# Box-3_Electronics_v5.net
KiCad netlist of a schematic drawn in EAGLE
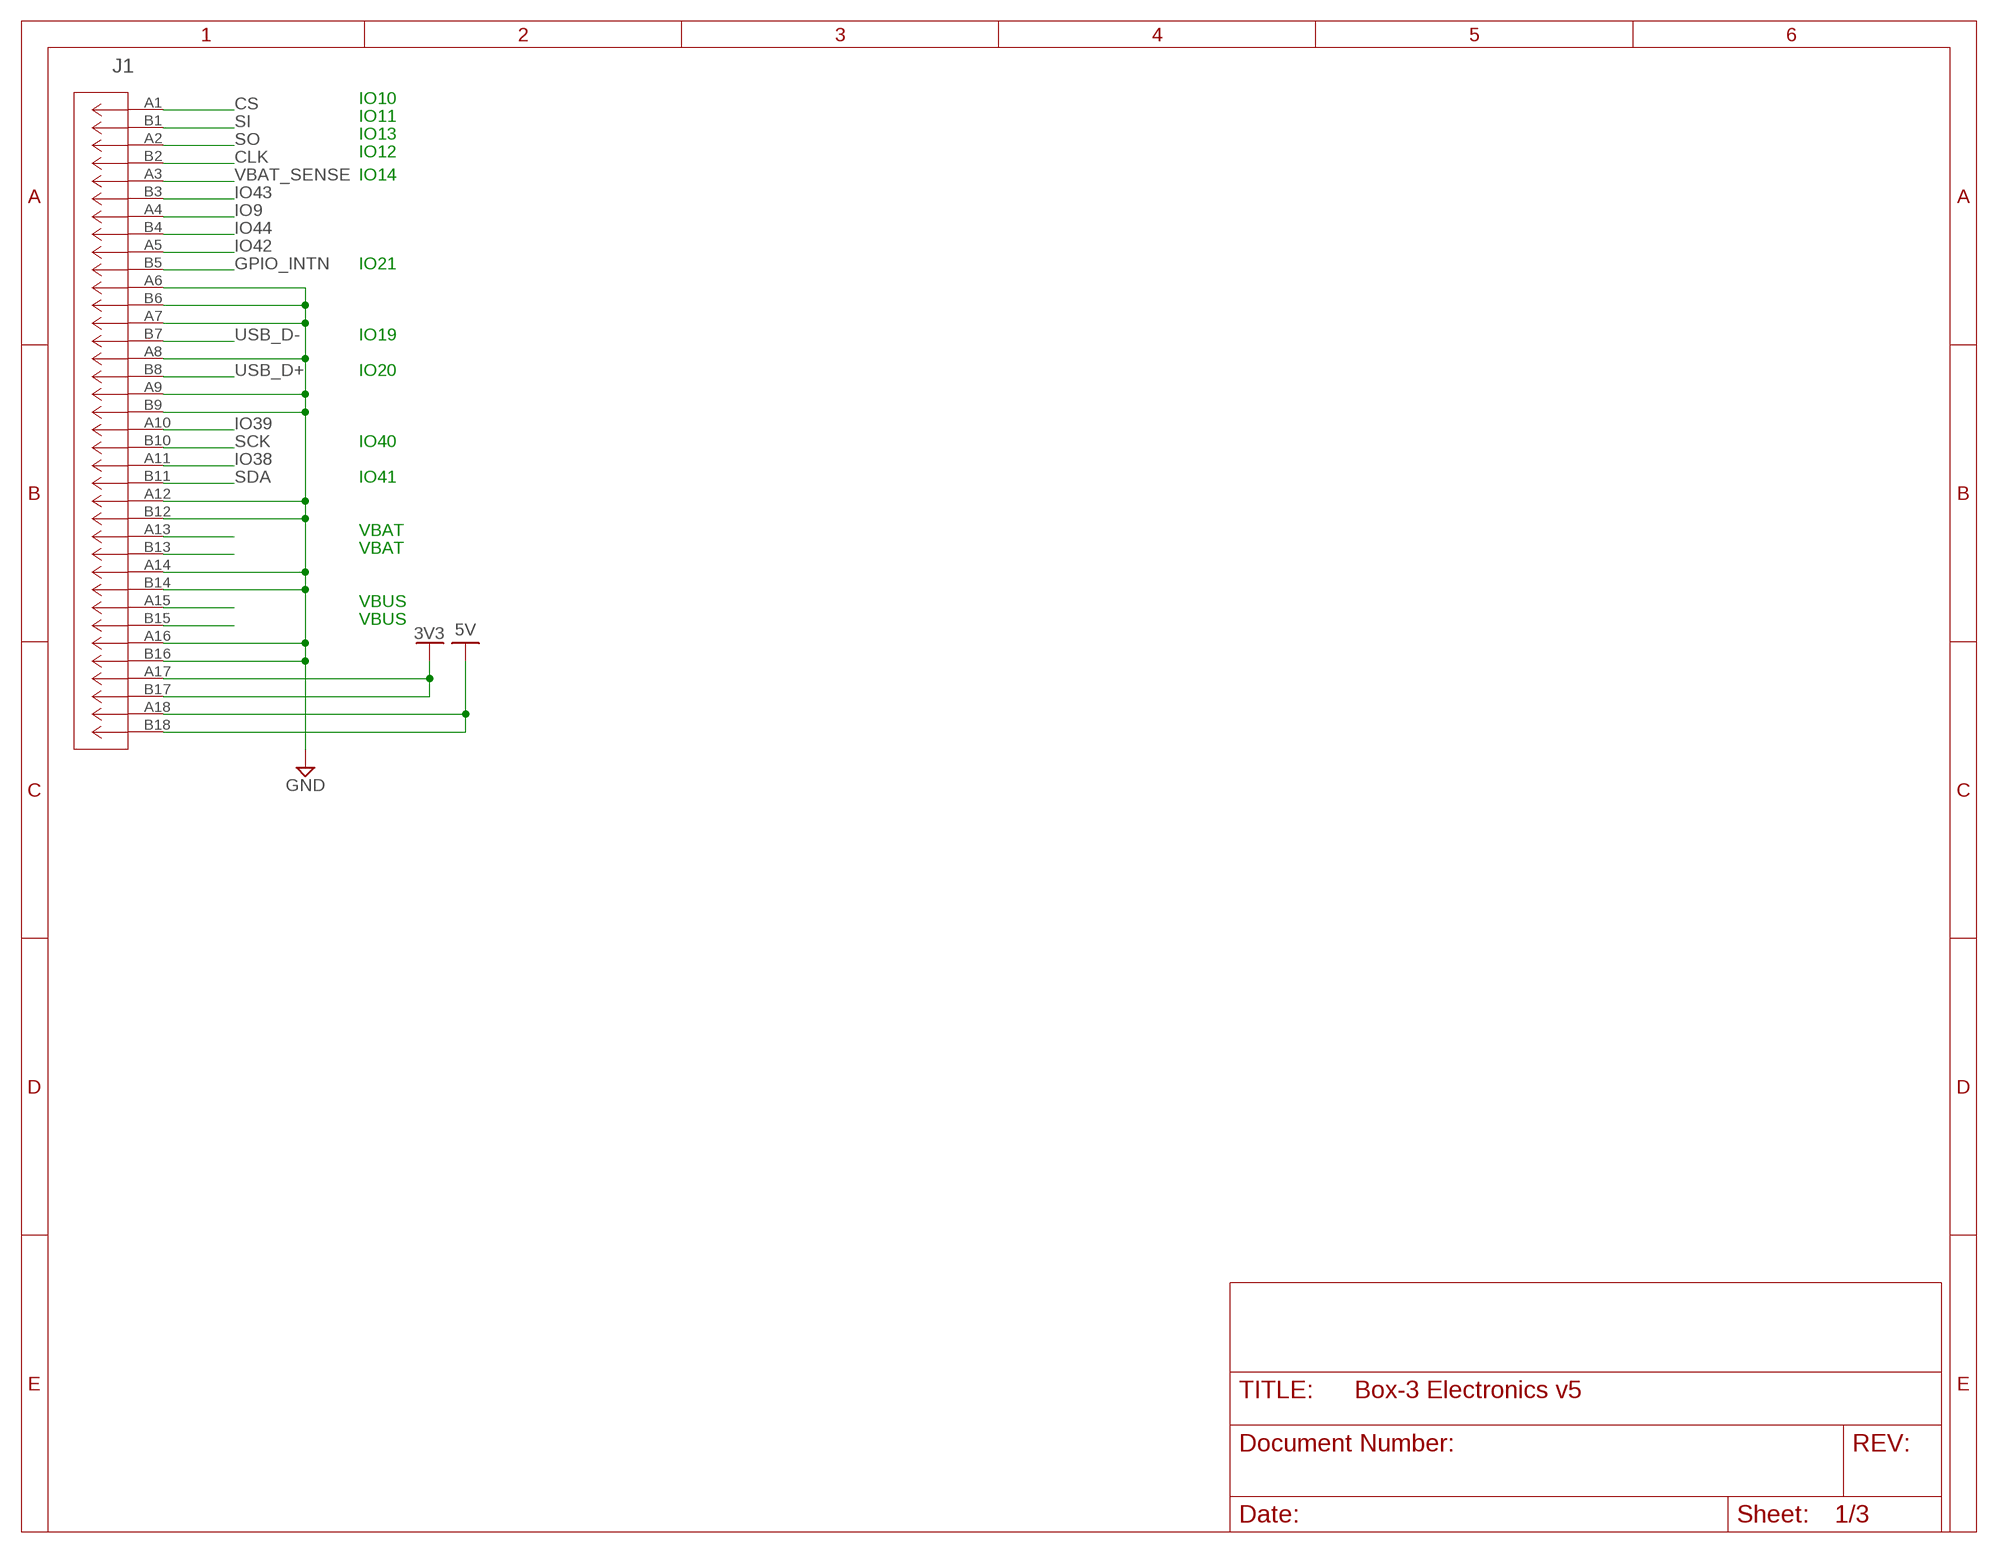
[diagram p0: schematic, sheet 1]
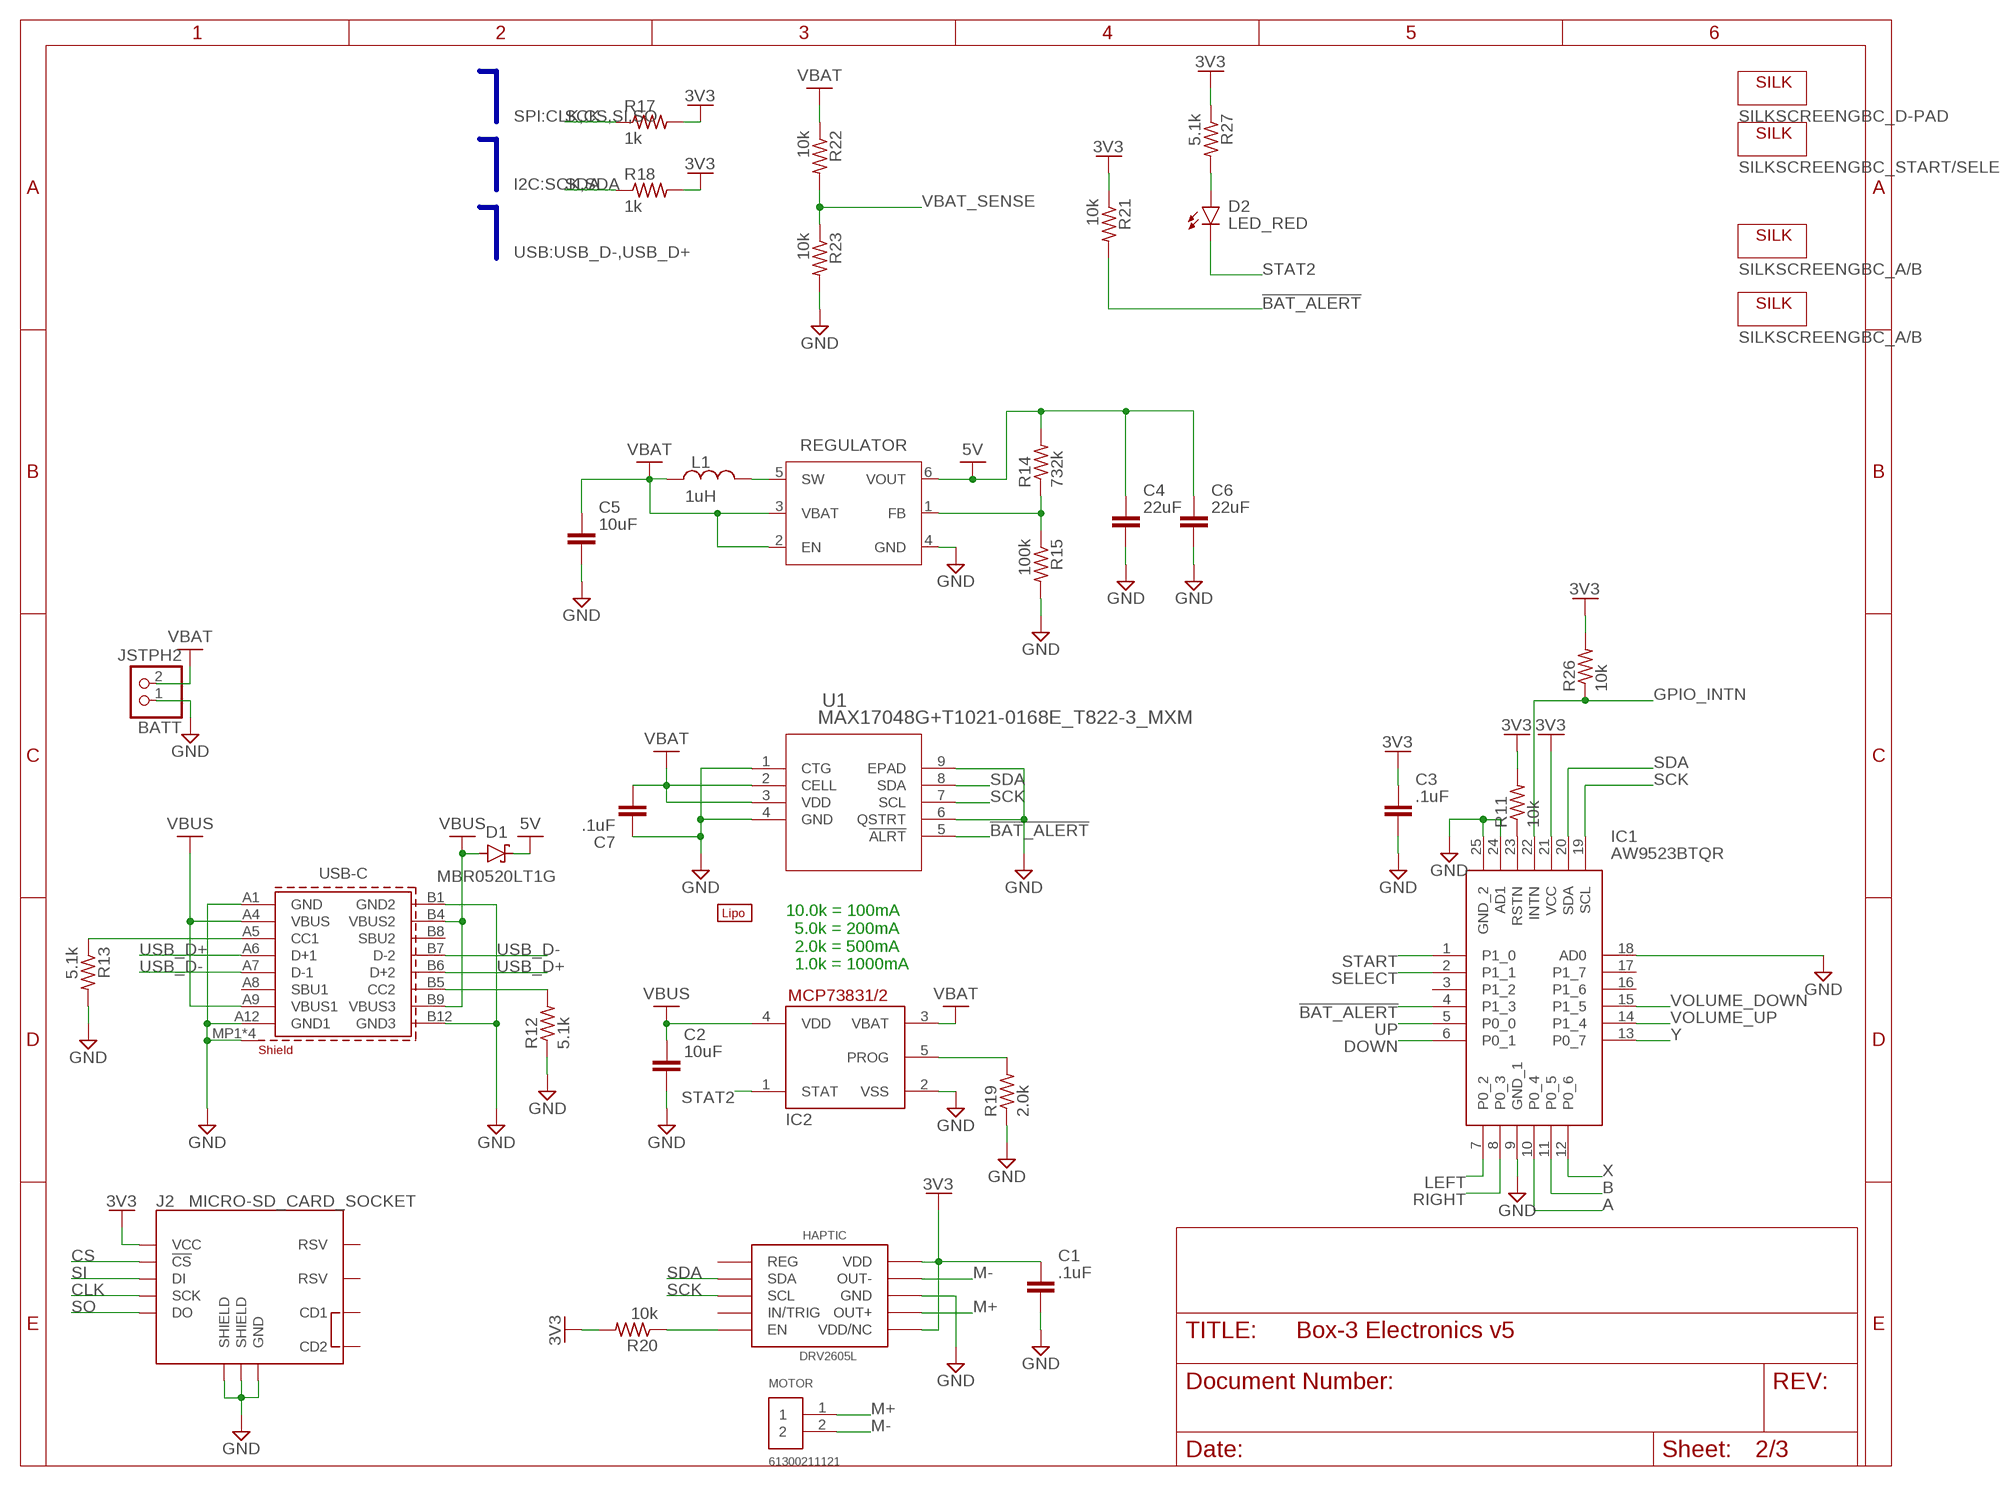
[diagram p1: schematic, sheet 2]
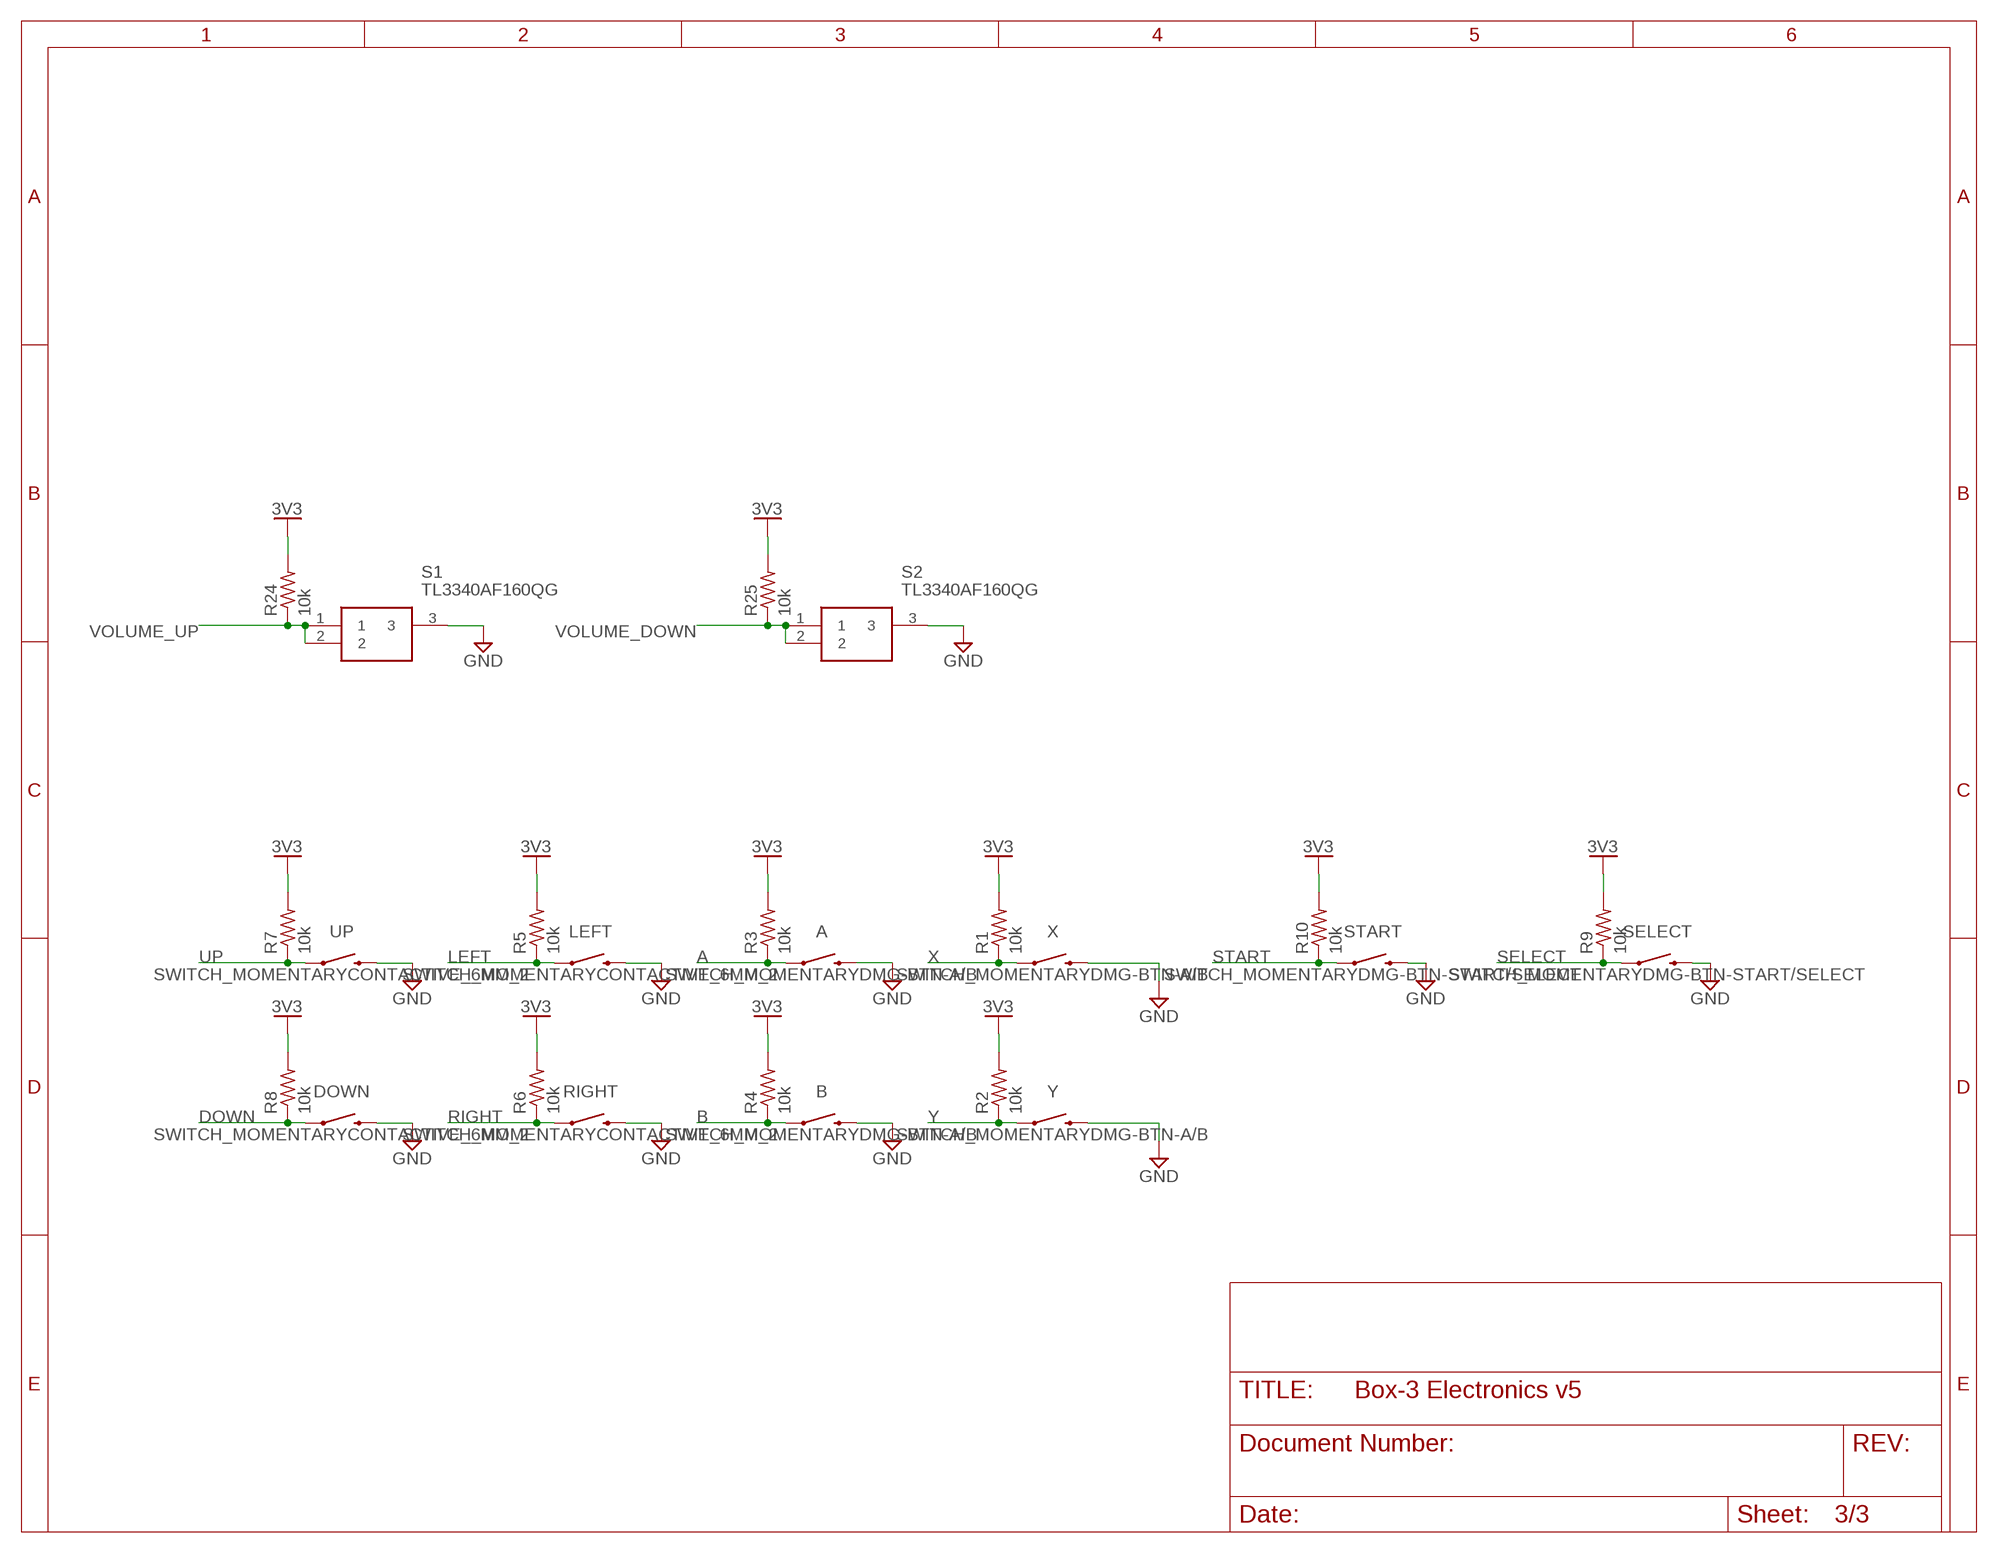
[diagram p2: schematic, sheet 3]

(export (version "E")
  (design (tool "Eeschema 10.0.6"))
  (components
    (comp (ref "BATT")
      (value "JSTPH2")
      (footprint "eagle-import:JSTPH2")
      (libsource (lib "eagle-import") (part "JSTPH2"))
    )
    (comp (ref "BT1")
      (value "LIPO-OUTLINE1100")
      (footprint "eagle-import:LIPO-1000")
      (libsource (lib "eagle-import") (part "LIPO-OUTLINE1100"))
    )
    (comp (ref "C1")
      (value ".1uF")
      (footprint "eagle-import:CAPC1608X85")
      (libsource (lib "eagle-import") (part "CCHIP-0603(1608-METRIC)_"))
    )
    (comp (ref "C2")
      (value "10uF")
      (footprint "eagle-import:CAPC1608X85")
      (libsource (lib "eagle-import") (part "CCHIP-0603(1608-METRIC)_"))
    )
    (comp (ref "C3")
      (value ".1uF")
      (footprint "eagle-import:CAPC1608X85")
      (libsource (lib "eagle-import") (part "CCHIP-0603(1608-METRIC)_"))
    )
    (comp (ref "C4")
      (value "22uF")
      (footprint "eagle-import:CAPC2012X110")
      (libsource (lib "eagle-import") (part "CCHIP-0805(2012-METRIC)_"))
    )
    (comp (ref "C5")
      (value "10uF")
      (footprint "eagle-import:CAPC1608X85")
      (libsource (lib "eagle-import") (part "CCHIP-0603(1608-METRIC)_"))
    )
    (comp (ref "C6")
      (value "22uF")
      (footprint "eagle-import:CAPC2012X110")
      (libsource (lib "eagle-import") (part "CCHIP-0805(2012-METRIC)_"))
    )
    (comp (ref "C7")
      (value ".1uF")
      (footprint "eagle-import:CAPC1608X85")
      (libsource (lib "eagle-import") (part "CCHIP-0603(1608-METRIC)_"))
    )
    (comp (ref "D1")
      (value "MBR0520LT1G")
      (footprint "eagle-import:SODFL3718X115")
      (fields (field (name "MANUFACTURER") "ON Semiconductor"))
      (libsource (lib "eagle-import") (part "SCHOTTKY_DO-219MBR0520LT1G"))
    )
    (comp (ref "D2")
      (value "LED_RED")
      (footprint "eagle-import:LEDC2012X110N_FLAT-R")
      (libsource (lib "eagle-import") (part "CHIP-FLAT-R_0805"))
    )
    (comp (ref "HAPTIC")
      (value "DRV2605L")
      (footprint "eagle-import:VSSOP-10")
      (libsource (lib "eagle-import") (part "DRV2605L"))
    )
    (comp (ref "IC1")
      (value "AW9523BTQR")
      (footprint "eagle-import:QFN50P400X400X80-25N")
      (libsource (lib "eagle-import") (part "AW9523BTQR"))
    )
    (comp (ref "IC2")
      (value "MCP73831/OT")
      (footprint "eagle-import:SOT23-5L")
      (libsource (lib "eagle-import") (part "MCP73831/OT"))
    )
    (comp (ref "J2")
      (value "MICRO-SD_CARD_SOCKET")
      (footprint "eagle-import:MICRO-SD-SOCKET")
      (libsource (lib "eagle-import") (part "MICRO-SD_CARD_SOCKET"))
    )
    (comp (ref "L1")
      (value "1uH")
      (footprint "eagle-import:INDC2009X120")
      (libsource (lib "eagle-import") (part "LCHIP-0805(2012-METRIC)_"))
    )
    (comp (ref "MOTOR")
      (value "61300211121")
      (footprint "eagle-import:61300211121")
      (fields
        (field (name "DIGI_KEY_PART_NUMBER") "732-5315-ND")
        (field (name "MANUFACTURER") "Wurth Electronics Inc.")
        (field (name "CREATED_BY") "PCBLayout.com")
      )
      (libsource (lib "eagle-import") (part "61300211121"))
    )
    (comp (ref "R11")
      (value "10k")
      (footprint "eagle-import:RESC1608X60")
      (libsource (lib "eagle-import") (part "R-USCHIP-0603(1608-METRIC)_"))
    )
    (comp (ref "R12")
      (value "5.1k")
      (footprint "eagle-import:RESC1608X60")
      (libsource (lib "eagle-import") (part "R-USCHIP-0603(1608-METRIC)_"))
    )
    (comp (ref "R13")
      (value "5.1k")
      (footprint "eagle-import:RESC1608X60")
      (libsource (lib "eagle-import") (part "R-USCHIP-0603(1608-METRIC)_"))
    )
    (comp (ref "R14")
      (value "732k")
      (footprint "eagle-import:RESC1608X60")
      (libsource (lib "eagle-import") (part "R-USCHIP-0603(1608-METRIC)_"))
    )
    (comp (ref "R15")
      (value "100k")
      (footprint "eagle-import:RESC1608X60")
      (libsource (lib "eagle-import") (part "R-USCHIP-0603(1608-METRIC)_"))
    )
    (comp (ref "R17")
      (value "1k")
      (footprint "eagle-import:RESC1608X60")
      (libsource (lib "eagle-import") (part "R-USCHIP-0603(1608-METRIC)_"))
    )
    (comp (ref "R18")
      (value "1k")
      (footprint "eagle-import:RESC1608X60")
      (libsource (lib "eagle-import") (part "R-USCHIP-0603(1608-METRIC)_"))
    )
    (comp (ref "R19")
      (value "2.0k")
      (footprint "eagle-import:RESC1608X60")
      (libsource (lib "eagle-import") (part "R-USCHIP-0603(1608-METRIC)_"))
    )
    (comp (ref "R20")
      (value "10k")
      (footprint "eagle-import:RESC1608X60")
      (libsource (lib "eagle-import") (part "R-USCHIP-0603(1608-METRIC)_"))
    )
    (comp (ref "R21")
      (value "10k")
      (footprint "eagle-import:RESC1608X60")
      (libsource (lib "eagle-import") (part "R-USCHIP-0603(1608-METRIC)_"))
    )
    (comp (ref "R22")
      (value "10k")
      (footprint "eagle-import:RESC1608X60")
      (libsource (lib "eagle-import") (part "R-USCHIP-0603(1608-METRIC)_"))
    )
    (comp (ref "R23")
      (value "10k")
      (footprint "eagle-import:RESC1608X60")
      (libsource (lib "eagle-import") (part "R-USCHIP-0603(1608-METRIC)_"))
    )
    (comp (ref "R26")
      (value "10k")
      (footprint "eagle-import:RESC1608X60")
      (libsource (lib "eagle-import") (part "R-USCHIP-0603(1608-METRIC)_"))
    )
    (comp (ref "R27")
      (value "5.1k")
      (footprint "eagle-import:RESC1608X60")
      (libsource (lib "eagle-import") (part "R-USCHIP-0603(1608-METRIC)_"))
    )
    (comp (ref "REGULATOR")
      (value "TPS61070")
      (footprint "eagle-import:SOT563")
      (libsource (lib "eagle-import") (part "TPS61023"))
    )
    (comp (ref "U$1")
      (value "SILKSCREENGBC_D-PAD")
      (footprint "eagle-import:GAMEBOY_COLOR_DPAD_SILK")
      (libsource (lib "eagle-import") (part "SILKSCREENGBC_D-PAD"))
    )
    (comp (ref "U$2")
      (value "SILKSCREENGBC_START/SELECT")
      (footprint "eagle-import:GAMEBOY_COLOR_START_SELECT_SILK")
      (libsource (lib "eagle-import") (part "SILKSCREENGBC_START/SELECT"))
    )
    (comp (ref "U$3")
      (value "SILKSCREENGBC_A/B")
      (footprint "eagle-import:GAMEBOY_COLOR_A_B_BUTTON_MEMBRANE")
      (libsource (lib "eagle-import") (part "SILKSCREENGBC_A/B"))
    )
    (comp (ref "U$4")
      (value "SILKSCREENGBC_A/B")
      (footprint "eagle-import:GAMEBOY_COLOR_A_B_BUTTON_MEMBRANE")
      (libsource (lib "eagle-import") (part "SILKSCREENGBC_A/B"))
    )
    (comp (ref "U1")
      (value "MAX17048G+T1021-0168E_T822-3_MXM")
      (footprint "eagle-import:21-0168E_T822-3_MXM")
      (fields
        (field (name "MANUFACTURER_PART_NUMBER") "MAX17048G+T10")
        (field (name "COPYRIGHT") "Copyright (C) 2023 Ultra Librarian. All rights reserved.")
      )
      (libsource (lib "eagle-import") (part "MAX17048G+T1021-0168E_T822-3_MXM"))
    )
    (comp (ref "USB-C")
      (value "629722000214")
      (footprint "eagle-import:USB4110GFA")
      (libsource (lib "eagle-import") (part "629722000214SMD"))
    )
    (comp (ref "A")
      (value "SWITCH_MOMENTARYDMG-BTN-A/B")
      (footprint "eagle-import:DMG_BTN3")
      (libsource (lib "eagle-import") (part "SWITCH_MOMENTARYDMG-BTN-A/B"))
    )
    (comp (ref "B")
      (value "SWITCH_MOMENTARYDMG-BTN-A/B")
      (footprint "eagle-import:DMG_BTN3")
      (libsource (lib "eagle-import") (part "SWITCH_MOMENTARYDMG-BTN-A/B"))
    )
    (comp (ref "DOWN")
      (value "SWITCH_MOMENTARYCONTACTIVE_6MM_2")
      (footprint "eagle-import:BUTTON-CONDUCTIVE_6MM_2")
      (libsource (lib "eagle-import") (part "SWITCH_MOMENTARYCONTACTIVE_6MM_2"))
    )
    (comp (ref "LEFT")
      (value "SWITCH_MOMENTARYCONTACTIVE_6MM_2")
      (footprint "eagle-import:BUTTON-CONDUCTIVE_6MM_2")
      (libsource (lib "eagle-import") (part "SWITCH_MOMENTARYCONTACTIVE_6MM_2"))
    )
    (comp (ref "R1")
      (value "10k")
      (footprint "eagle-import:RESC1608X60")
      (libsource (lib "eagle-import") (part "R-USCHIP-0603(1608-METRIC)_"))
    )
    (comp (ref "R2")
      (value "10k")
      (footprint "eagle-import:RESC1608X60")
      (libsource (lib "eagle-import") (part "R-USCHIP-0603(1608-METRIC)_"))
    )
    (comp (ref "R3")
      (value "10k")
      (footprint "eagle-import:RESC1608X60")
      (libsource (lib "eagle-import") (part "R-USCHIP-0603(1608-METRIC)_"))
    )
    (comp (ref "R4")
      (value "10k")
      (footprint "eagle-import:RESC1608X60")
      (libsource (lib "eagle-import") (part "R-USCHIP-0603(1608-METRIC)_"))
    )
    (comp (ref "R5")
      (value "10k")
      (footprint "eagle-import:RESC1608X60")
      (libsource (lib "eagle-import") (part "R-USCHIP-0603(1608-METRIC)_"))
    )
    (comp (ref "R6")
      (value "10k")
      (footprint "eagle-import:RESC1608X60")
      (libsource (lib "eagle-import") (part "R-USCHIP-0603(1608-METRIC)_"))
    )
    (comp (ref "R7")
      (value "10k")
      (footprint "eagle-import:RESC1608X60")
      (libsource (lib "eagle-import") (part "R-USCHIP-0603(1608-METRIC)_"))
    )
    (comp (ref "R8")
      (value "10k")
      (footprint "eagle-import:RESC1608X60")
      (libsource (lib "eagle-import") (part "R-USCHIP-0603(1608-METRIC)_"))
    )
    (comp (ref "R9")
      (value "10k")
      (footprint "eagle-import:RESC1608X60")
      (libsource (lib "eagle-import") (part "R-USCHIP-0603(1608-METRIC)_"))
    )
    (comp (ref "R10")
      (value "10k")
      (footprint "eagle-import:RESC1608X60")
      (libsource (lib "eagle-import") (part "R-USCHIP-0603(1608-METRIC)_"))
    )
    (comp (ref "R24")
      (value "10k")
      (footprint "eagle-import:RESC1608X60")
      (libsource (lib "eagle-import") (part "R-USCHIP-0603(1608-METRIC)_"))
    )
    (comp (ref "R25")
      (value "10k")
      (footprint "eagle-import:RESC1608X60")
      (libsource (lib "eagle-import") (part "R-USCHIP-0603(1608-METRIC)_"))
    )
    (comp (ref "RIGHT")
      (value "SWITCH_MOMENTARYCONTACTIVE_6MM_2")
      (footprint "eagle-import:BUTTON-CONDUCTIVE_6MM_2")
      (libsource (lib "eagle-import") (part "SWITCH_MOMENTARYCONTACTIVE_6MM_2"))
    )
    (comp (ref "S1")
      (value "TL3340AF160QG")
      (footprint "eagle-import:TL3340")
      (fields (field (name "MOUSER_PART_NUMBER") "612-TL3340AF160QG"))
      (libsource (lib "eagle-import") (part "TL3340AF160QG"))
    )
    (comp (ref "S2")
      (value "TL3340AF160QG")
      (footprint "eagle-import:TL3340")
      (fields (field (name "MOUSER_PART_NUMBER") "612-TL3340AF160QG"))
      (libsource (lib "eagle-import") (part "TL3340AF160QG"))
    )
    (comp (ref "SELECT")
      (value "SWITCH_MOMENTARYDMG-BTN-START/SELECT")
      (footprint "eagle-import:DMG_BTN1_W2")
      (libsource (lib "eagle-import") (part "SWITCH_MOMENTARYDMG-BTN-START/SELECT"))
    )
    (comp (ref "START")
      (value "SWITCH_MOMENTARYDMG-BTN-START/SELECT")
      (footprint "eagle-import:DMG_BTN1_W2")
      (libsource (lib "eagle-import") (part "SWITCH_MOMENTARYDMG-BTN-START/SELECT"))
    )
    (comp (ref "UP")
      (value "SWITCH_MOMENTARYCONTACTIVE_6MM_2")
      (footprint "eagle-import:BUTTON-CONDUCTIVE_6MM_2")
      (libsource (lib "eagle-import") (part "SWITCH_MOMENTARYCONTACTIVE_6MM_2"))
    )
    (comp (ref "X")
      (value "SWITCH_MOMENTARYDMG-BTN-A/B")
      (footprint "eagle-import:DMG_BTN3")
      (libsource (lib "eagle-import") (part "SWITCH_MOMENTARYDMG-BTN-A/B"))
    )
    (comp (ref "Y")
      (value "SWITCH_MOMENTARYDMG-BTN-A/B")
      (footprint "eagle-import:DMG_BTN3")
      (libsource (lib "eagle-import") (part "SWITCH_MOMENTARYDMG-BTN-A/B"))
    )
    (comp (ref "J1")
      (value "5-1734857-1CONN_5-1734857-1_TEC")
      (footprint "eagle-import:CONN_5-1734857-1_TEC")
      (fields
        (field (name "MANUFACTURER_PART_NUMBER") "5-1734857-1")
        (field (name "COPYRIGHT") "Copyright (C) 2023 Ultra Librarian. All rights reserved.")
      )
      (libsource (lib "eagle-import") (part "5-1734857-1CONN_5-1734857-1_TEC"))
    )
  )
  (nets
    (net (code "7") (name "3V3") (class "Default")
      (node (ref "C1") (pin "1") (pinfunction "1_1") (pintype "passive"))
      (node (ref "C3") (pin "1") (pinfunction "1_1") (pintype "passive"))
      (node (ref "HAPTIC") (pin "P$10") (pinfunction "VDD_P$10") (pintype "bidirectional"))
      (node (ref "HAPTIC") (pin "P$6") (pinfunction "VDD/NC_P$6") (pintype "bidirectional"))
      (node (ref "IC1") (pin "21") (pinfunction "VCC_21") (pintype "bidirectional"))
      (node (ref "J1") (pin "A17") (pinfunction "A17_A17") (pintype "passive"))
      (node (ref "J1") (pin "B17") (pinfunction "B17_B17") (pintype "passive"))
      (node (ref "J2") (pin "VCC") (pinfunction "VCC_VCC") (pintype "bidirectional"))
      (node (ref "R1") (pin "2") (pinfunction "2_2") (pintype "passive"))
      (node (ref "R10") (pin "2") (pinfunction "2_2") (pintype "passive"))
      (node (ref "R11") (pin "2") (pinfunction "2_2") (pintype "passive"))
      (node (ref "R17") (pin "2") (pinfunction "2_2") (pintype "passive"))
      (node (ref "R18") (pin "2") (pinfunction "2_2") (pintype "passive"))
      (node (ref "R2") (pin "2") (pinfunction "2_2") (pintype "passive"))
      (node (ref "R20") (pin "2") (pinfunction "2_2") (pintype "passive"))
      (node (ref "R21") (pin "1") (pinfunction "1_1") (pintype "passive"))
      (node (ref "R24") (pin "2") (pinfunction "2_2") (pintype "passive"))
      (node (ref "R25") (pin "2") (pinfunction "2_2") (pintype "passive"))
      (node (ref "R26") (pin "2") (pinfunction "2_2") (pintype "passive"))
      (node (ref "R27") (pin "1") (pinfunction "1_1") (pintype "passive"))
      (node (ref "R3") (pin "2") (pinfunction "2_2") (pintype "passive"))
      (node (ref "R4") (pin "2") (pinfunction "2_2") (pintype "passive"))
      (node (ref "R5") (pin "2") (pinfunction "2_2") (pintype "passive"))
      (node (ref "R6") (pin "2") (pinfunction "2_2") (pintype "passive"))
      (node (ref "R7") (pin "2") (pinfunction "2_2") (pintype "passive"))
      (node (ref "R8") (pin "2") (pinfunction "2_2") (pintype "passive"))
      (node (ref "R9") (pin "2") (pinfunction "2_2") (pintype "passive"))
    )
    (net (code "8") (name "5V") (class "Default")
      (node (ref "C4") (pin "1") (pinfunction "1_1") (pintype "passive"))
      (node (ref "C6") (pin "1") (pinfunction "1_1") (pintype "passive"))
      (node (ref "D1") (pin "1") (pinfunction "C_1") (pintype "passive"))
      (node (ref "J1") (pin "A18") (pinfunction "A18_A18") (pintype "passive"))
      (node (ref "J1") (pin "B18") (pinfunction "B18_B18") (pintype "passive"))
      (node (ref "R14") (pin "2") (pinfunction "2_2") (pintype "passive"))
      (node (ref "REGULATOR") (pin "6") (pinfunction "VOUT_6") (pintype "output"))
    )
    (net (code "9") (name "A") (class "Default")
      (node (ref "A") (pin "P$1") (pinfunction "1_P$1") (pintype "passive"))
      (node (ref "A") (pin "P$3") (pinfunction "1_P$3") (pintype "passive"))
      (node (ref "IC1") (pin "10") (pinfunction "P0_4_10") (pintype "bidirectional"))
      (node (ref "R3") (pin "1") (pinfunction "1_1") (pintype "passive"))
    )
    (net (code "10") (name "B") (class "Default")
      (node (ref "B") (pin "P$1") (pinfunction "1_P$1") (pintype "passive"))
      (node (ref "B") (pin "P$3") (pinfunction "1_P$3") (pintype "passive"))
      (node (ref "IC1") (pin "11") (pinfunction "P0_5_11") (pintype "bidirectional"))
      (node (ref "R4") (pin "1") (pinfunction "1_1") (pintype "passive"))
    )
    (net (code "11") (name "CLK") (class "Default")
      (node (ref "J1") (pin "B2") (pinfunction "B2_B2") (pintype "passive"))
      (node (ref "J2") (pin "SCLK") (pinfunction "SCK_SCLK") (pintype "bidirectional"))
    )
    (net (code "12") (name "CS") (class "Default")
      (node (ref "J1") (pin "A1") (pinfunction "A1_A1") (pintype "passive"))
      (node (ref "J2") (pin "CS") (pinfunction "~{CS}_CS") (pintype "bidirectional"))
    )
    (net (code "13") (name "DOWN") (class "Default")
      (node (ref "DOWN") (pin "1") (pinfunction "1_1") (pintype "passive"))
      (node (ref "IC1") (pin "6") (pinfunction "P0_1_6") (pintype "bidirectional"))
      (node (ref "R8") (pin "1") (pinfunction "1_1") (pintype "passive"))
    )
    (net (code "14") (name "GND") (class "Default")
      (node (ref "A") (pin "P$2") (pinfunction "2_P$2") (pintype "passive"))
      (node (ref "A") (pin "P$4") (pinfunction "2_P$4") (pintype "passive"))
      (node (ref "B") (pin "P$2") (pinfunction "2_P$2") (pintype "passive"))
      (node (ref "B") (pin "P$4") (pinfunction "2_P$4") (pintype "passive"))
      (node (ref "BATT") (pin "1") (pinfunction "1_1") (pintype "passive"))
      (node (ref "C1") (pin "2") (pinfunction "2_2") (pintype "passive"))
      (node (ref "C2") (pin "2") (pinfunction "2_2") (pintype "passive"))
      (node (ref "C3") (pin "2") (pinfunction "2_2") (pintype "passive"))
      (node (ref "C4") (pin "2") (pinfunction "2_2") (pintype "passive"))
      (node (ref "C5") (pin "2") (pinfunction "2_2") (pintype "passive"))
      (node (ref "C6") (pin "2") (pinfunction "2_2") (pintype "passive"))
      (node (ref "C7") (pin "1") (pinfunction "1_1") (pintype "passive"))
      (node (ref "DOWN") (pin "2") (pinfunction "2_2") (pintype "passive"))
      (node (ref "HAPTIC") (pin "P$8") (pinfunction "GND_P$8") (pintype "bidirectional"))
      (node (ref "IC1") (pin "18") (pinfunction "AD0_18") (pintype "bidirectional"))
      (node (ref "IC1") (pin "24") (pinfunction "AD1_24") (pintype "bidirectional"))
      (node (ref "IC1") (pin "25") (pinfunction "GND_2_25") (pintype "bidirectional"))
      (node (ref "IC1") (pin "9") (pinfunction "GND_1_9") (pintype "bidirectional"))
      (node (ref "IC2") (pin "2") (pinfunction "VSS_2") (pintype "power_in"))
      (node (ref "J1") (pin "A12") (pinfunction "A12_A12") (pintype "passive"))
      (node (ref "J1") (pin "A14") (pinfunction "A14_A14") (pintype "passive"))
      (node (ref "J1") (pin "A16") (pinfunction "A16_A16") (pintype "passive"))
      (node (ref "J1") (pin "A6") (pinfunction "A6_A6") (pintype "passive"))
      (node (ref "J1") (pin "A7") (pinfunction "A7_A7") (pintype "passive"))
      (node (ref "J1") (pin "A8") (pinfunction "A8_A8") (pintype "passive"))
      (node (ref "J1") (pin "A9") (pinfunction "A9_A9") (pintype "passive"))
      (node (ref "J1") (pin "B12") (pinfunction "B12_B12") (pintype "passive"))
      (node (ref "J1") (pin "B14") (pinfunction "B14_B14") (pintype "passive"))
      (node (ref "J1") (pin "B16") (pinfunction "B16_B16") (pintype "passive"))
      (node (ref "J1") (pin "B6") (pinfunction "B6_B6") (pintype "passive"))
      (node (ref "J1") (pin "B9") (pinfunction "B9_B9") (pintype "passive"))
      (node (ref "J2") (pin "GND") (pinfunction "GND_GND") (pintype "bidirectional"))
      (node (ref "J2") (pin "GND1") (pinfunction "SHIELD_GND1") (pintype "bidirectional"))
      (node (ref "J2") (pin "GND3") (pinfunction "SHIELD_GND3") (pintype "bidirectional"))
      (node (ref "LEFT") (pin "2") (pinfunction "2_2") (pintype "passive"))
      (node (ref "R12") (pin "1") (pinfunction "1_1") (pintype "passive"))
      (node (ref "R13") (pin "2") (pinfunction "2_2") (pintype "passive"))
      (node (ref "R15") (pin "2") (pinfunction "2_2") (pintype "passive"))
      (node (ref "R19") (pin "1") (pinfunction "1_1") (pintype "passive"))
      (node (ref "R23") (pin "2") (pinfunction "2_2") (pintype "passive"))
      (node (ref "REGULATOR") (pin "4") (pinfunction "GND_4") (pintype "power_in"))
      (node (ref "RIGHT") (pin "2") (pinfunction "2_2") (pintype "passive"))
      (node (ref "S1") (pin "3") (pinfunction "3_3") (pintype "bidirectional"))
      (node (ref "S2") (pin "3") (pinfunction "3_3") (pintype "bidirectional"))
      (node (ref "SELECT") (pin "P$2") (pinfunction "2_P$2") (pintype "passive"))
      (node (ref "SELECT") (pin "P$4") (pinfunction "2_P$4") (pintype "passive"))
      (node (ref "START") (pin "P$2") (pinfunction "2_P$2") (pintype "passive"))
      (node (ref "START") (pin "P$4") (pinfunction "2_P$4") (pintype "passive"))
      (node (ref "U1") (pin "1") (pinfunction "CTG_1") (pintype "passive"))
      (node (ref "U1") (pin "4") (pinfunction "GND_4") (pintype "power_in"))
      (node (ref "U1") (pin "6") (pinfunction "QSTRT_6") (pintype "input"))
      (node (ref "U1") (pin "9") (pinfunction "EPAD_9") (pintype "passive"))
      (node (ref "UP") (pin "2") (pinfunction "2_2") (pintype "passive"))
      (node (ref "USB-C") (pin "A1") (pinfunction "GND_A1") (pintype "passive"))
      (node (ref "USB-C") (pin "A12") (pinfunction "GND1_A12") (pintype "passive"))
      (node (ref "USB-C") (pin "B1") (pinfunction "GND2_B1") (pintype "passive"))
      (node (ref "USB-C") (pin "B12") (pinfunction "GND3_B12") (pintype "passive"))
      (node (ref "USB-C") (pin "MP1") (pinfunction "SHIELD_MP1") (pintype "passive"))
      (node (ref "USB-C") (pin "MP2") (pinfunction "SHIELD_MP2") (pintype "passive"))
      (node (ref "USB-C") (pin "MP3") (pinfunction "SHIELD_MP3") (pintype "passive"))
      (node (ref "USB-C") (pin "MP4") (pinfunction "SHIELD_MP4") (pintype "passive"))
      (node (ref "X") (pin "P$2") (pinfunction "2_P$2") (pintype "passive"))
      (node (ref "X") (pin "P$4") (pinfunction "2_P$4") (pintype "passive"))
      (node (ref "Y") (pin "P$2") (pinfunction "2_P$2") (pintype "passive"))
      (node (ref "Y") (pin "P$4") (pinfunction "2_P$4") (pintype "passive"))
    )
    (net (code "15") (name "GPIO_INTN") (class "Default")
      (node (ref "IC1") (pin "22") (pinfunction "INTN_22") (pintype "bidirectional"))
      (node (ref "J1") (pin "B5") (pinfunction "B5_B5") (pintype "passive"))
      (node (ref "R26") (pin "1") (pinfunction "1_1") (pintype "passive"))
    )
    (net (code "16") (name "IO9") (class "Default")
      (node (ref "J1") (pin "A4") (pinfunction "A4_A4") (pintype "passive"))
    )
    (net (code "17") (name "IO38") (class "Default")
      (node (ref "J1") (pin "A11") (pinfunction "A11_A11") (pintype "passive"))
    )
    (net (code "18") (name "IO39") (class "Default")
      (node (ref "J1") (pin "A10") (pinfunction "A10_A10") (pintype "passive"))
    )
    (net (code "19") (name "IO42") (class "Default")
      (node (ref "J1") (pin "A5") (pinfunction "A5_A5") (pintype "passive"))
    )
    (net (code "20") (name "IO43") (class "Default")
      (node (ref "J1") (pin "B3") (pinfunction "B3_B3") (pintype "passive"))
    )
    (net (code "21") (name "IO44") (class "Default")
      (node (ref "J1") (pin "B4") (pinfunction "B4_B4") (pintype "passive"))
    )
    (net (code "22") (name "LEFT") (class "Default")
      (node (ref "IC1") (pin "7") (pinfunction "P0_2_7") (pintype "bidirectional"))
      (node (ref "LEFT") (pin "1") (pinfunction "1_1") (pintype "passive"))
      (node (ref "R5") (pin "1") (pinfunction "1_1") (pintype "passive"))
    )
    (net (code "23") (name "M+") (class "Default")
      (node (ref "HAPTIC") (pin "P$7") (pinfunction "OUT+_P$7") (pintype "bidirectional"))
      (node (ref "MOTOR") (pin "1") (pinfunction "1_1") (pintype "passive"))
    )
    (net (code "24") (name "M-") (class "Default")
      (node (ref "HAPTIC") (pin "P$9") (pinfunction "OUT-_P$9") (pintype "bidirectional"))
      (node (ref "MOTOR") (pin "2") (pinfunction "2_2") (pintype "passive"))
    )
    (net (code "25") (name "Net-(D2-PadA)") (class "Default")
      (node (ref "D2") (pin "A") (pinfunction "A_A") (pintype "passive"))
      (node (ref "R27") (pin "2") (pinfunction "2_2") (pintype "passive"))
    )
    (net (code "26") (name "Net-(HAPTIC-EN)") (class "Default")
      (node (ref "HAPTIC") (pin "P$5") (pinfunction "EN_P$5") (pintype "bidirectional"))
      (node (ref "R20") (pin "1") (pinfunction "1_1") (pintype "passive"))
    )
    (net (code "27") (name "Net-(IC1-RSTN)") (class "Default")
      (node (ref "IC1") (pin "23") (pinfunction "RSTN_23") (pintype "bidirectional"))
      (node (ref "R11") (pin "1") (pinfunction "1_1") (pintype "passive"))
    )
    (net (code "28") (name "Net-(IC2-PROG)") (class "Default")
      (node (ref "IC2") (pin "5") (pinfunction "PROG_5") (pintype "input"))
      (node (ref "R19") (pin "2") (pinfunction "2_2") (pintype "passive"))
    )
    (net (code "29") (name "Net-(REGULATOR-FB)") (class "Default")
      (node (ref "R14") (pin "1") (pinfunction "1_1") (pintype "passive"))
      (node (ref "R15") (pin "1") (pinfunction "1_1") (pintype "passive"))
      (node (ref "REGULATOR") (pin "1") (pinfunction "FB_1") (pintype "input"))
    )
    (net (code "30") (name "Net-(REGULATOR-SW)") (class "Default")
      (node (ref "L1") (pin "2") (pinfunction "2_2") (pintype "passive"))
      (node (ref "REGULATOR") (pin "5") (pinfunction "SW_5") (pintype "input"))
    )
    (net (code "31") (name "Net-(USB-C-CC1)") (class "Default")
      (node (ref "R13") (pin "1") (pinfunction "1_1") (pintype "passive"))
      (node (ref "USB-C") (pin "A5") (pinfunction "CC1_A5") (pintype "passive"))
    )
    (net (code "32") (name "Net-(USB-C-CC2)") (class "Default")
      (node (ref "R12") (pin "2") (pinfunction "2_2") (pintype "passive"))
      (node (ref "USB-C") (pin "B5") (pinfunction "CC2_B5") (pintype "passive"))
    )
    (net (code "33") (name "RIGHT") (class "Default")
      (node (ref "IC1") (pin "8") (pinfunction "P0_3_8") (pintype "bidirectional"))
      (node (ref "R6") (pin "1") (pinfunction "1_1") (pintype "passive"))
      (node (ref "RIGHT") (pin "1") (pinfunction "1_1") (pintype "passive"))
    )
    (net (code "34") (name "SCK") (class "Default")
      (node (ref "HAPTIC") (pin "P$2") (pinfunction "SCL_P$2") (pintype "bidirectional"))
      (node (ref "IC1") (pin "19") (pinfunction "SCL_19") (pintype "bidirectional"))
      (node (ref "J1") (pin "B10") (pinfunction "B10_B10") (pintype "passive"))
      (node (ref "R17") (pin "1") (pinfunction "1_1") (pintype "passive"))
      (node (ref "U1") (pin "7") (pinfunction "SCL_7") (pintype "input"))
    )
    (net (code "35") (name "SDA") (class "Default")
      (node (ref "HAPTIC") (pin "P$3") (pinfunction "SDA_P$3") (pintype "bidirectional"))
      (node (ref "IC1") (pin "20") (pinfunction "SDA_20") (pintype "bidirectional"))
      (node (ref "J1") (pin "B11") (pinfunction "B11_B11") (pintype "passive"))
      (node (ref "R18") (pin "1") (pinfunction "1_1") (pintype "passive"))
      (node (ref "U1") (pin "8") (pinfunction "SDA_8") (pintype "bidirectional"))
    )
    (net (code "36") (name "SELECT") (class "Default")
      (node (ref "IC1") (pin "2") (pinfunction "P1_1_2") (pintype "bidirectional"))
      (node (ref "R9") (pin "1") (pinfunction "1_1") (pintype "passive"))
      (node (ref "SELECT") (pin "P$1") (pinfunction "1_P$1") (pintype "passive"))
      (node (ref "SELECT") (pin "P$3") (pinfunction "1_P$3") (pintype "passive"))
    )
    (net (code "37") (name "SI") (class "Default")
      (node (ref "J1") (pin "B1") (pinfunction "B1_B1") (pintype "passive"))
      (node (ref "J2") (pin "DI") (pinfunction "DI_DI") (pintype "bidirectional"))
    )
    (net (code "38") (name "SO") (class "Default")
      (node (ref "J1") (pin "A2") (pinfunction "A2_A2") (pintype "passive"))
      (node (ref "J2") (pin "DO") (pinfunction "DO_DO") (pintype "bidirectional"))
    )
    (net (code "39") (name "START") (class "Default")
      (node (ref "IC1") (pin "1") (pinfunction "P1_0_1") (pintype "bidirectional"))
      (node (ref "R10") (pin "1") (pinfunction "1_1") (pintype "passive"))
      (node (ref "START") (pin "P$1") (pinfunction "1_P$1") (pintype "passive"))
      (node (ref "START") (pin "P$3") (pinfunction "1_P$3") (pintype "passive"))
    )
    (net (code "40") (name "STAT2") (class "Default")
      (node (ref "D2") (pin "C") (pinfunction "C_C") (pintype "passive"))
      (node (ref "IC2") (pin "1") (pinfunction "STAT_1") (pintype "output"))
    )
    (net (code "41") (name "UP") (class "Default")
      (node (ref "IC1") (pin "5") (pinfunction "P0_0_5") (pintype "bidirectional"))
      (node (ref "R7") (pin "1") (pinfunction "1_1") (pintype "passive"))
      (node (ref "UP") (pin "1") (pinfunction "1_1") (pintype "passive"))
    )
    (net (code "42") (name "USB_D+") (class "Default")
      (node (ref "J1") (pin "B8") (pinfunction "B8_B8") (pintype "passive"))
      (node (ref "USB-C") (pin "A6") (pinfunction "D+1_A6") (pintype "passive"))
      (node (ref "USB-C") (pin "B6") (pinfunction "D+2_B6") (pintype "passive"))
    )
    (net (code "43") (name "USB_D-") (class "Default")
      (node (ref "J1") (pin "B7") (pinfunction "B7_B7") (pintype "passive"))
      (node (ref "USB-C") (pin "A7") (pinfunction "D-1_A7") (pintype "passive"))
      (node (ref "USB-C") (pin "B7") (pinfunction "D-2_B7") (pintype "passive"))
    )
    (net (code "44") (name "VBAT") (class "Default")
      (node (ref "BATT") (pin "2") (pinfunction "2_2") (pintype "passive"))
      (node (ref "C5") (pin "1") (pinfunction "1_1") (pintype "passive"))
      (node (ref "C7") (pin "2") (pinfunction "2_2") (pintype "passive"))
      (node (ref "IC2") (pin "3") (pinfunction "VBAT_3") (pintype "bidirectional"))
      (node (ref "L1") (pin "1") (pinfunction "1_1") (pintype "passive"))
      (node (ref "R22") (pin "1") (pinfunction "1_1") (pintype "passive"))
      (node (ref "REGULATOR") (pin "2") (pinfunction "EN_2") (pintype "input"))
      (node (ref "REGULATOR") (pin "3") (pinfunction "VBAT_3") (pintype "input"))
      (node (ref "U1") (pin "2") (pinfunction "CELL_2") (pintype "passive"))
      (node (ref "U1") (pin "3") (pinfunction "VDD_3") (pintype "power_in"))
    )
    (net (code "45") (name "VBAT_SENSE") (class "Default")
      (node (ref "J1") (pin "A3") (pinfunction "A3_A3") (pintype "passive"))
      (node (ref "R22") (pin "2") (pinfunction "2_2") (pintype "passive"))
      (node (ref "R23") (pin "1") (pinfunction "1_1") (pintype "passive"))
    )
    (net (code "46") (name "VBUS") (class "Default")
      (node (ref "C2") (pin "1") (pinfunction "1_1") (pintype "passive"))
      (node (ref "D1") (pin "2") (pinfunction "A_2") (pintype "passive"))
      (node (ref "IC2") (pin "4") (pinfunction "VDD_4") (pintype "power_in"))
      (node (ref "USB-C") (pin "A4") (pinfunction "VBUS_A4") (pintype "passive"))
      (node (ref "USB-C") (pin "A9") (pinfunction "VBUS1_A9") (pintype "passive"))
      (node (ref "USB-C") (pin "B4") (pinfunction "VBUS2_B4") (pintype "passive"))
      (node (ref "USB-C") (pin "B9") (pinfunction "VBUS3_B9") (pintype "passive"))
    )
    (net (code "47") (name "VOLUME_DOWN") (class "Default")
      (node (ref "IC1") (pin "15") (pinfunction "P1_5_15") (pintype "bidirectional"))
      (node (ref "R25") (pin "1") (pinfunction "1_1") (pintype "passive"))
      (node (ref "S2") (pin "1") (pinfunction "1_1") (pintype "bidirectional"))
      (node (ref "S2") (pin "2") (pinfunction "2_2") (pintype "bidirectional"))
    )
    (net (code "48") (name "VOLUME_UP") (class "Default")
      (node (ref "IC1") (pin "14") (pinfunction "P1_4_14") (pintype "bidirectional"))
      (node (ref "R24") (pin "1") (pinfunction "1_1") (pintype "passive"))
      (node (ref "S1") (pin "1") (pinfunction "1_1") (pintype "bidirectional"))
      (node (ref "S1") (pin "2") (pinfunction "2_2") (pintype "bidirectional"))
    )
    (net (code "49") (name "X") (class "Default")
      (node (ref "IC1") (pin "12") (pinfunction "P0_6_12") (pintype "bidirectional"))
      (node (ref "R1") (pin "1") (pinfunction "1_1") (pintype "passive"))
      (node (ref "X") (pin "P$1") (pinfunction "1_P$1") (pintype "passive"))
      (node (ref "X") (pin "P$3") (pinfunction "1_P$3") (pintype "passive"))
    )
    (net (code "50") (name "Y") (class "Default")
      (node (ref "IC1") (pin "13") (pinfunction "P0_7_13") (pintype "bidirectional"))
      (node (ref "R2") (pin "1") (pinfunction "1_1") (pintype "passive"))
      (node (ref "Y") (pin "P$1") (pinfunction "1_P$1") (pintype "passive"))
      (node (ref "Y") (pin "P$3") (pinfunction "1_P$3") (pintype "passive"))
    )
    (net (code "51") (name "unconnected-(HAPTIC-IN{slash}TRIG-PadP$4)") (class "Default")
      (node (ref "HAPTIC") (pin "P$4") (pinfunction "IN/TRIG_P$4") (pintype "bidirectional"))
    )
    (net (code "52") (name "unconnected-(HAPTIC-REG-PadP$1)") (class "Default")
      (node (ref "HAPTIC") (pin "P$1") (pinfunction "REG_P$1") (pintype "bidirectional"))
    )
    (net (code "53") (name "unconnected-(IC1-P1_2-Pad3)") (class "Default")
      (node (ref "IC1") (pin "3") (pinfunction "P1_2_3") (pintype "bidirectional"))
    )
    (net (code "54") (name "unconnected-(IC1-P1_6-Pad16)") (class "Default")
      (node (ref "IC1") (pin "16") (pinfunction "P1_6_16") (pintype "bidirectional"))
    )
    (net (code "55") (name "unconnected-(IC1-P1_7-Pad17)") (class "Default")
      (node (ref "IC1") (pin "17") (pinfunction "P1_7_17") (pintype "bidirectional"))
    )
    (net (code "56") (name "unconnected-(J1-PadA13)") (class "Default")
      (node (ref "J1") (pin "A13") (pinfunction "A13_A13") (pintype "passive"))
    )
    (net (code "57") (name "unconnected-(J1-PadA15)") (class "Default")
      (node (ref "J1") (pin "A15") (pinfunction "A15_A15") (pintype "passive"))
    )
    (net (code "58") (name "unconnected-(J1-PadB13)") (class "Default")
      (node (ref "J1") (pin "B13") (pinfunction "B13_B13") (pintype "passive"))
    )
    (net (code "59") (name "unconnected-(J1-PadB15)") (class "Default")
      (node (ref "J1") (pin "B15") (pinfunction "B15_B15") (pintype "passive"))
    )
    (net (code "60") (name "unconnected-(J2-PadCD1)") (class "Default")
      (node (ref "J2") (pin "CD1") (pinfunction "CD1_CD1") (pintype "bidirectional"))
    )
    (net (code "61") (name "unconnected-(J2-PadCD2)") (class "Default")
      (node (ref "J2") (pin "CD2") (pinfunction "CD2_CD2") (pintype "bidirectional"))
    )
    (net (code "62") (name "unconnected-(J2-RSV-PadRSV1)") (class "Default")
      (node (ref "J2") (pin "RSV1") (pinfunction "RSV_RSV1") (pintype "bidirectional"))
    )
    (net (code "63") (name "unconnected-(J2-RSV-PadRSV2)") (class "Default")
      (node (ref "J2") (pin "RSV2") (pinfunction "RSV_RSV2") (pintype "bidirectional"))
    )
    (net (code "64") (name "unconnected-(USB-C-SBU1-PadA8)") (class "Default")
      (node (ref "USB-C") (pin "A8") (pinfunction "SBU1_A8") (pintype "passive"))
    )
    (net (code "65") (name "unconnected-(USB-C-SBU2-PadB8)") (class "Default")
      (node (ref "USB-C") (pin "B8") (pinfunction "SBU2_B8") (pintype "passive"))
    )
    (net (code "66") (name "~{BAT_ALERT}") (class "Default")
      (node (ref "IC1") (pin "4") (pinfunction "P1_3_4") (pintype "bidirectional"))
      (node (ref "R21") (pin "2") (pinfunction "2_2") (pintype "passive"))
      (node (ref "U1") (pin "5") (pinfunction "~{ALRT}_5") (pintype "output"))
    )
  )
)
